# LPCB218_-_HEC1-4.net
KiCad netlist of a schematic drawn in Altium Designer
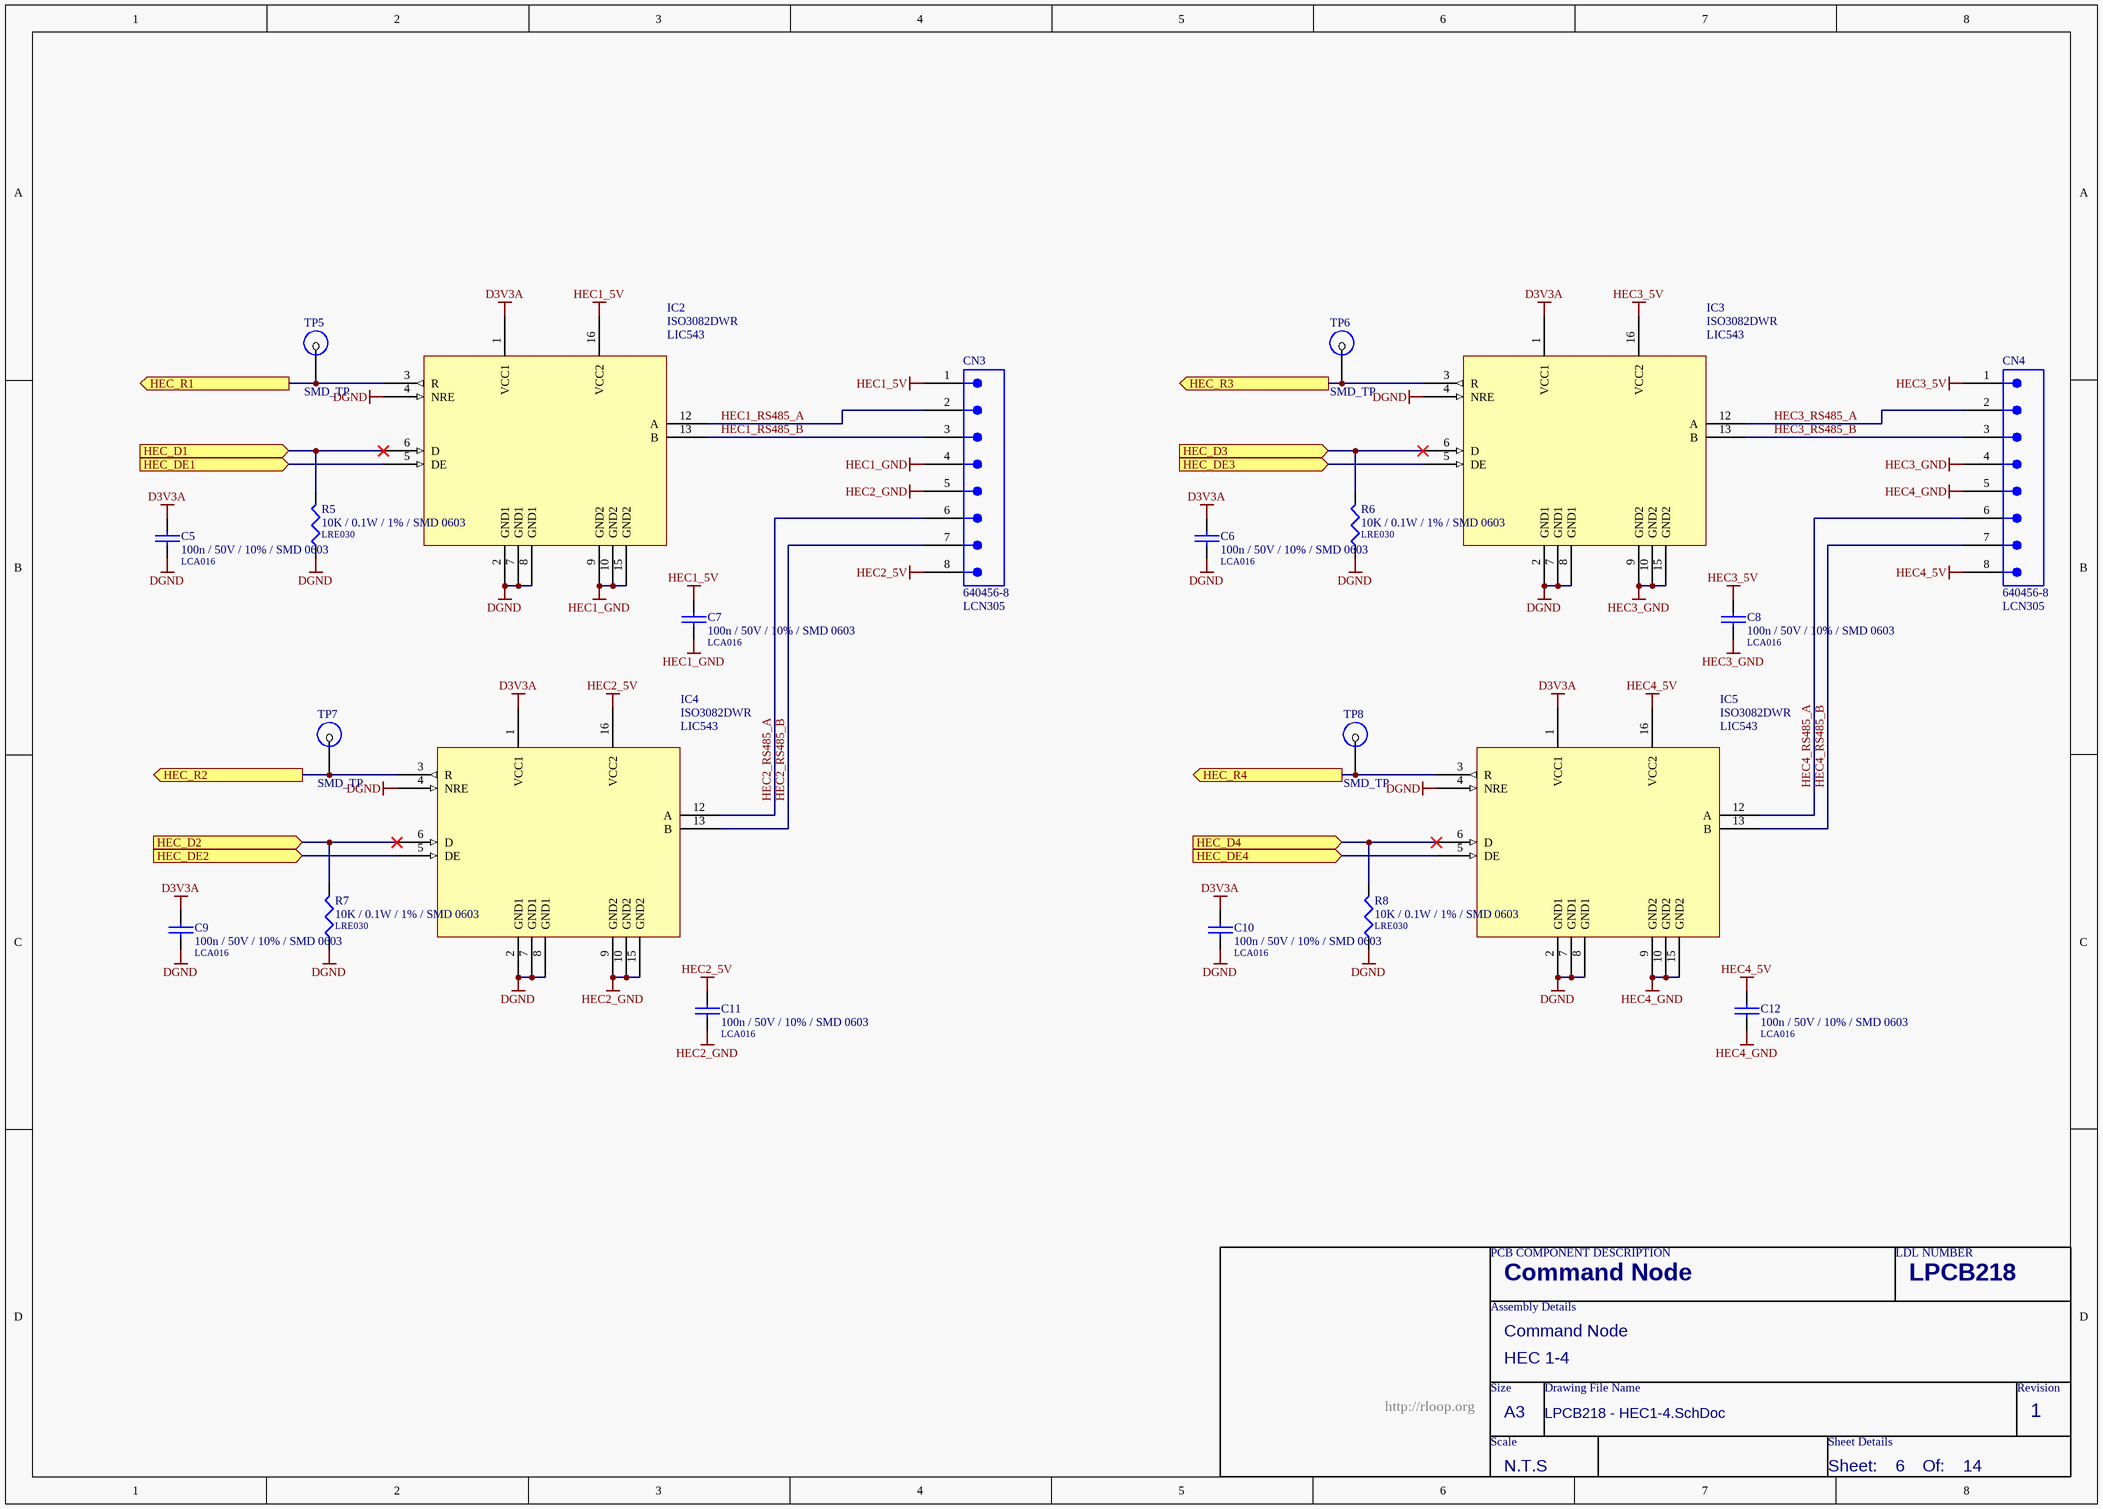
[diagram p0: LPCB218 - HEC1-4.SchDoc]

(export (version "E")
  (design (tool "Eeschema 10.0.6"))
  (components
    (comp (ref "C5")
      (value "100n / 50V / 10% / SMD 0603")
      (footprint "LFP011__CC1608-0603-IPC7351_B")
      (description "Capacitor, Ceramic Chip, 100nF (0.1uF), 50V, 5%, SMD 0603 [LCA016]")
      (fields (field (name "LDL_NUMBER") "LCA016"))
      (libsource (lib "LDL_Capacitors") (part "100n / 50V / 10% / SMD 0603"))
    )
    (comp (ref "C6")
      (value "100n / 50V / 10% / SMD 0603")
      (footprint "LFP011__CC1608-0603-IPC7351_B")
      (description "Capacitor, Ceramic Chip, 100nF (0.1uF), 50V, 5%, SMD 0603 [LCA016]")
      (fields (field (name "LDL_NUMBER") "LCA016"))
      (libsource (lib "LDL_Capacitors") (part "100n / 50V / 10% / SMD 0603"))
    )
    (comp (ref "C7")
      (value "100n / 50V / 10% / SMD 0603")
      (footprint "LFP011__CC1608-0603-IPC7351_B")
      (description "Capacitor, Ceramic Chip, 100nF (0.1uF), 50V, 5%, SMD 0603 [LCA016]")
      (fields (field (name "LDL_NUMBER") "LCA016"))
      (libsource (lib "LDL_Capacitors") (part "100n / 50V / 10% / SMD 0603"))
    )
    (comp (ref "C8")
      (value "100n / 50V / 10% / SMD 0603")
      (footprint "LFP011__CC1608-0603-IPC7351_B")
      (description "Capacitor, Ceramic Chip, 100nF (0.1uF), 50V, 5%, SMD 0603 [LCA016]")
      (fields (field (name "LDL_NUMBER") "LCA016"))
      (libsource (lib "LDL_Capacitors") (part "100n / 50V / 10% / SMD 0603"))
    )
    (comp (ref "C9")
      (value "100n / 50V / 10% / SMD 0603")
      (footprint "LFP011__CC1608-0603-IPC7351_B")
      (description "Capacitor, Ceramic Chip, 100nF (0.1uF), 50V, 5%, SMD 0603 [LCA016]")
      (fields (field (name "LDL_NUMBER") "LCA016"))
      (libsource (lib "LDL_Capacitors") (part "100n / 50V / 10% / SMD 0603"))
    )
    (comp (ref "C10")
      (value "100n / 50V / 10% / SMD 0603")
      (footprint "LFP011__CC1608-0603-IPC7351_B")
      (description "Capacitor, Ceramic Chip, 100nF (0.1uF), 50V, 5%, SMD 0603 [LCA016]")
      (fields (field (name "LDL_NUMBER") "LCA016"))
      (libsource (lib "LDL_Capacitors") (part "100n / 50V / 10% / SMD 0603"))
    )
    (comp (ref "C11")
      (value "100n / 50V / 10% / SMD 0603")
      (footprint "LFP011__CC1608-0603-IPC7351_B")
      (description "Capacitor, Ceramic Chip, 100nF (0.1uF), 50V, 5%, SMD 0603 [LCA016]")
      (fields (field (name "LDL_NUMBER") "LCA016"))
      (libsource (lib "LDL_Capacitors") (part "100n / 50V / 10% / SMD 0603"))
    )
    (comp (ref "C12")
      (value "100n / 50V / 10% / SMD 0603")
      (footprint "LFP011__CC1608-0603-IPC7351_B")
      (description "Capacitor, Ceramic Chip, 100nF (0.1uF), 50V, 5%, SMD 0603 [LCA016]")
      (fields (field (name "LDL_NUMBER") "LCA016"))
      (libsource (lib "LDL_Capacitors") (part "100n / 50V / 10% / SMD 0603"))
    )
    (comp (ref "CN3")
      (value "640456-8")
      (footprint "640456-8")
      (description "Connector, Male Header, 8 Way")
      (fields (field (name "LDL_NUMBER") "LCN305"))
      (libsource (lib "LDL_Connectors") (part "640456-8"))
    )
    (comp (ref "CN4")
      (value "640456-8")
      (footprint "640456-8")
      (description "Connector, Male Header, 8 Way")
      (fields (field (name "LDL_NUMBER") "LCN305"))
      (libsource (lib "LDL_Connectors") (part "640456-8"))
    )
    (comp (ref "IC2")
      (value "ISO3082DWR")
      (footprint "LFP068__SO-G16/G6.9")
      (description "IC, RS485 Isolator, SMD SOIC 16 [LIC543]")
      (fields (field (name "LDL_NUMBER") "LIC543"))
      (libsource (lib "LDL_Semiconductors") (part "ISO3082DWR"))
    )
    (comp (ref "IC3")
      (value "ISO3082DWR")
      (footprint "LFP068__SO-G16/G6.9")
      (description "IC, RS485 Isolator, SMD SOIC 16 [LIC543]")
      (fields (field (name "LDL_NUMBER") "LIC543"))
      (libsource (lib "LDL_Semiconductors") (part "ISO3082DWR"))
    )
    (comp (ref "IC4")
      (value "ISO3082DWR")
      (footprint "LFP068__SO-G16/G6.9")
      (description "IC, RS485 Isolator, SMD SOIC 16 [LIC543]")
      (fields (field (name "LDL_NUMBER") "LIC543"))
      (libsource (lib "LDL_Semiconductors") (part "ISO3082DWR"))
    )
    (comp (ref "IC5")
      (value "ISO3082DWR")
      (footprint "LFP068__SO-G16/G6.9")
      (description "IC, RS485 Isolator, SMD SOIC 16 [LIC543]")
      (fields (field (name "LDL_NUMBER") "LIC543"))
      (libsource (lib "LDL_Semiconductors") (part "ISO3082DWR"))
    )
    (comp (ref "R5")
      (value "10K / 0.1W / 1% / SMD 0603")
      (footprint "LFP020__CR1608-0603-IPC7351_B")
      (description "Resistor, Ceramic Chip, 10K, 0.1W, 1%, SMD 0603 [LRE030]")
      (fields (field (name "LDL_NUMBER") "LRE030"))
      (libsource (lib "LDL_Resistors") (part "10K / 0.1W / 1% / SMD 0603"))
    )
    (comp (ref "R6")
      (value "10K / 0.1W / 1% / SMD 0603")
      (footprint "LFP020__CR1608-0603-IPC7351_B")
      (description "Resistor, Ceramic Chip, 10K, 0.1W, 1%, SMD 0603 [LRE030]")
      (fields (field (name "LDL_NUMBER") "LRE030"))
      (libsource (lib "LDL_Resistors") (part "10K / 0.1W / 1% / SMD 0603"))
    )
    (comp (ref "R7")
      (value "10K / 0.1W / 1% / SMD 0603")
      (footprint "LFP020__CR1608-0603-IPC7351_B")
      (description "Resistor, Ceramic Chip, 10K, 0.1W, 1%, SMD 0603 [LRE030]")
      (fields (field (name "LDL_NUMBER") "LRE030"))
      (libsource (lib "LDL_Resistors") (part "10K / 0.1W / 1% / SMD 0603"))
    )
    (comp (ref "R8")
      (value "10K / 0.1W / 1% / SMD 0603")
      (footprint "LFP020__CR1608-0603-IPC7351_B")
      (description "Resistor, Ceramic Chip, 10K, 0.1W, 1%, SMD 0603 [LRE030]")
      (fields (field (name "LDL_NUMBER") "LRE030"))
      (libsource (lib "LDL_Resistors") (part "10K / 0.1W / 1% / SMD 0603"))
    )
    (comp (ref "TP5")
      (value "SMD_TP")
      (footprint "SMD-TP")
      (description "SMD Test Point")
      (libsource (lib "LDL_Connectors") (part "SMD_TP"))
    )
    (comp (ref "TP6")
      (value "SMD_TP")
      (footprint "SMD-TP")
      (description "SMD Test Point")
      (libsource (lib "LDL_Connectors") (part "SMD_TP"))
    )
    (comp (ref "TP7")
      (value "SMD_TP")
      (footprint "SMD-TP")
      (description "SMD Test Point")
      (libsource (lib "LDL_Connectors") (part "SMD_TP"))
    )
    (comp (ref "TP8")
      (value "SMD_TP")
      (footprint "SMD-TP")
      (description "SMD Test Point")
      (libsource (lib "LDL_Connectors") (part "SMD_TP"))
    )
  )
  (nets
    (net (code "1") (name "/HEC1_RS485_A") (class "Default")
      (node (ref "CN3") (pin "2") (pinfunction "2_2") (pintype "passive"))
      (node (ref "IC2") (pin "12") (pinfunction "A_12") (pintype "passive"))
    )
    (net (code "2") (name "/HEC1_RS485_B") (class "Default")
      (node (ref "CN3") (pin "3") (pinfunction "3_3") (pintype "passive"))
      (node (ref "IC2") (pin "13") (pinfunction "B_13") (pintype "passive"))
    )
    (net (code "3") (name "/HEC2_RS485_A") (class "Default")
      (node (ref "CN3") (pin "6") (pinfunction "6_6") (pintype "passive"))
      (node (ref "IC4") (pin "12") (pinfunction "A_12") (pintype "passive"))
    )
    (net (code "4") (name "/HEC2_RS485_B") (class "Default")
      (node (ref "CN3") (pin "7") (pinfunction "7_7") (pintype "passive"))
      (node (ref "IC4") (pin "13") (pinfunction "B_13") (pintype "passive"))
    )
    (net (code "5") (name "/HEC3_RS485_A") (class "Default")
      (node (ref "CN4") (pin "2") (pinfunction "2_2") (pintype "passive"))
      (node (ref "IC3") (pin "12") (pinfunction "A_12") (pintype "passive"))
    )
    (net (code "6") (name "/HEC3_RS485_B") (class "Default")
      (node (ref "CN4") (pin "3") (pinfunction "3_3") (pintype "passive"))
      (node (ref "IC3") (pin "13") (pinfunction "B_13") (pintype "passive"))
    )
    (net (code "7") (name "/HEC4_RS485_A") (class "Default")
      (node (ref "CN4") (pin "6") (pinfunction "6_6") (pintype "passive"))
      (node (ref "IC5") (pin "12") (pinfunction "A_12") (pintype "passive"))
    )
    (net (code "8") (name "/HEC4_RS485_B") (class "Default")
      (node (ref "CN4") (pin "7") (pinfunction "7_7") (pintype "passive"))
      (node (ref "IC5") (pin "13") (pinfunction "B_13") (pintype "passive"))
    )
    (net (code "9") (name "/HEC_D1") (class "Default")
      (node (ref "IC2") (pin "6") (pinfunction "D_6") (pintype "input"))
      (node (ref "R5") (pin "2") (pintype "passive"))
    )
    (net (code "10") (name "/HEC_D2") (class "Default")
      (node (ref "IC4") (pin "6") (pinfunction "D_6") (pintype "input"))
      (node (ref "R7") (pin "2") (pintype "passive"))
    )
    (net (code "11") (name "/HEC_D3") (class "Default")
      (node (ref "IC3") (pin "6") (pinfunction "D_6") (pintype "input"))
      (node (ref "R6") (pin "2") (pintype "passive"))
    )
    (net (code "12") (name "/HEC_D4") (class "Default")
      (node (ref "IC5") (pin "6") (pinfunction "D_6") (pintype "input"))
      (node (ref "R8") (pin "2") (pintype "passive"))
    )
    (net (code "13") (name "/HEC_DE1") (class "Default")
      (node (ref "IC2") (pin "5") (pinfunction "DE_5") (pintype "input"))
    )
    (net (code "14") (name "/HEC_DE2") (class "Default")
      (node (ref "IC4") (pin "5") (pinfunction "DE_5") (pintype "input"))
    )
    (net (code "15") (name "/HEC_DE3") (class "Default")
      (node (ref "IC3") (pin "5") (pinfunction "DE_5") (pintype "input"))
    )
    (net (code "16") (name "/HEC_DE4") (class "Default")
      (node (ref "IC5") (pin "5") (pinfunction "DE_5") (pintype "input"))
    )
    (net (code "17") (name "/HEC_R1") (class "Default")
      (node (ref "IC2") (pin "3") (pinfunction "R_3") (pintype "output"))
      (node (ref "TP5") (pin "1") (pintype "passive"))
    )
    (net (code "18") (name "/HEC_R2") (class "Default")
      (node (ref "IC4") (pin "3") (pinfunction "R_3") (pintype "output"))
      (node (ref "TP7") (pin "1") (pintype "passive"))
    )
    (net (code "19") (name "/HEC_R3") (class "Default")
      (node (ref "IC3") (pin "3") (pinfunction "R_3") (pintype "output"))
      (node (ref "TP6") (pin "1") (pintype "passive"))
    )
    (net (code "20") (name "/HEC_R4") (class "Default")
      (node (ref "IC5") (pin "3") (pinfunction "R_3") (pintype "output"))
      (node (ref "TP8") (pin "1") (pintype "passive"))
    )
    (net (code "21") (name "D3V3A") (class "Default")
      (node (ref "C10") (pin "1") (pintype "passive"))
      (node (ref "C5") (pin "1") (pintype "passive"))
      (node (ref "C6") (pin "1") (pintype "passive"))
      (node (ref "C9") (pin "1") (pintype "passive"))
      (node (ref "IC2") (pin "1") (pinfunction "VCC1_1") (pintype "power_in"))
      (node (ref "IC3") (pin "1") (pinfunction "VCC1_1") (pintype "power_in"))
      (node (ref "IC4") (pin "1") (pinfunction "VCC1_1") (pintype "power_in"))
      (node (ref "IC5") (pin "1") (pinfunction "VCC1_1") (pintype "power_in"))
    )
    (net (code "22") (name "DGND") (class "Default")
      (node (ref "C10") (pin "2") (pintype "passive"))
      (node (ref "C5") (pin "2") (pintype "passive"))
      (node (ref "C6") (pin "2") (pintype "passive"))
      (node (ref "C9") (pin "2") (pintype "passive"))
      (node (ref "IC2") (pin "2") (pinfunction "GND1_2") (pintype "power_in"))
      (node (ref "IC2") (pin "4") (pinfunction "NRE_4") (pintype "input"))
      (node (ref "IC2") (pin "7") (pinfunction "GND1_7") (pintype "power_in"))
      (node (ref "IC2") (pin "8") (pinfunction "GND1_8") (pintype "power_in"))
      (node (ref "IC3") (pin "2") (pinfunction "GND1_2") (pintype "power_in"))
      (node (ref "IC3") (pin "4") (pinfunction "NRE_4") (pintype "input"))
      (node (ref "IC3") (pin "7") (pinfunction "GND1_7") (pintype "power_in"))
      (node (ref "IC3") (pin "8") (pinfunction "GND1_8") (pintype "power_in"))
      (node (ref "IC4") (pin "2") (pinfunction "GND1_2") (pintype "power_in"))
      (node (ref "IC4") (pin "4") (pinfunction "NRE_4") (pintype "input"))
      (node (ref "IC4") (pin "7") (pinfunction "GND1_7") (pintype "power_in"))
      (node (ref "IC4") (pin "8") (pinfunction "GND1_8") (pintype "power_in"))
      (node (ref "IC5") (pin "2") (pinfunction "GND1_2") (pintype "power_in"))
      (node (ref "IC5") (pin "4") (pinfunction "NRE_4") (pintype "input"))
      (node (ref "IC5") (pin "7") (pinfunction "GND1_7") (pintype "power_in"))
      (node (ref "IC5") (pin "8") (pinfunction "GND1_8") (pintype "power_in"))
      (node (ref "R5") (pin "1") (pintype "passive"))
      (node (ref "R6") (pin "1") (pintype "passive"))
      (node (ref "R7") (pin "1") (pintype "passive"))
      (node (ref "R8") (pin "1") (pintype "passive"))
    )
    (net (code "23") (name "HEC1_5V") (class "Default")
      (node (ref "C7") (pin "1") (pintype "passive"))
      (node (ref "CN3") (pin "1") (pinfunction "1_1") (pintype "passive"))
      (node (ref "IC2") (pin "16") (pinfunction "VCC2_16") (pintype "power_in"))
    )
    (net (code "24") (name "HEC1_GND") (class "Default")
      (node (ref "C7") (pin "2") (pintype "passive"))
      (node (ref "CN3") (pin "4") (pinfunction "4_4") (pintype "passive"))
      (node (ref "IC2") (pin "10") (pinfunction "GND2_10") (pintype "power_in"))
      (node (ref "IC2") (pin "15") (pinfunction "GND2_15") (pintype "power_in"))
      (node (ref "IC2") (pin "9") (pinfunction "GND2_9") (pintype "power_in"))
    )
    (net (code "25") (name "HEC2_5V") (class "Default")
      (node (ref "C11") (pin "1") (pintype "passive"))
      (node (ref "CN3") (pin "8") (pinfunction "8_8") (pintype "passive"))
      (node (ref "IC4") (pin "16") (pinfunction "VCC2_16") (pintype "power_in"))
    )
    (net (code "26") (name "HEC2_GND") (class "Default")
      (node (ref "C11") (pin "2") (pintype "passive"))
      (node (ref "CN3") (pin "5") (pinfunction "5_5") (pintype "passive"))
      (node (ref "IC4") (pin "10") (pinfunction "GND2_10") (pintype "power_in"))
      (node (ref "IC4") (pin "15") (pinfunction "GND2_15") (pintype "power_in"))
      (node (ref "IC4") (pin "9") (pinfunction "GND2_9") (pintype "power_in"))
    )
    (net (code "27") (name "HEC3_5V") (class "Default")
      (node (ref "C8") (pin "1") (pintype "passive"))
      (node (ref "CN4") (pin "1") (pinfunction "1_1") (pintype "passive"))
      (node (ref "IC3") (pin "16") (pinfunction "VCC2_16") (pintype "power_in"))
    )
    (net (code "28") (name "HEC3_GND") (class "Default")
      (node (ref "C8") (pin "2") (pintype "passive"))
      (node (ref "CN4") (pin "4") (pinfunction "4_4") (pintype "passive"))
      (node (ref "IC3") (pin "10") (pinfunction "GND2_10") (pintype "power_in"))
      (node (ref "IC3") (pin "15") (pinfunction "GND2_15") (pintype "power_in"))
      (node (ref "IC3") (pin "9") (pinfunction "GND2_9") (pintype "power_in"))
    )
    (net (code "29") (name "HEC4_5V") (class "Default")
      (node (ref "C12") (pin "1") (pintype "passive"))
      (node (ref "CN4") (pin "8") (pinfunction "8_8") (pintype "passive"))
      (node (ref "IC5") (pin "16") (pinfunction "VCC2_16") (pintype "power_in"))
    )
    (net (code "30") (name "HEC4_GND") (class "Default")
      (node (ref "C12") (pin "2") (pintype "passive"))
      (node (ref "CN4") (pin "5") (pinfunction "5_5") (pintype "passive"))
      (node (ref "IC5") (pin "10") (pinfunction "GND2_10") (pintype "power_in"))
      (node (ref "IC5") (pin "15") (pinfunction "GND2_15") (pintype "power_in"))
      (node (ref "IC5") (pin "9") (pinfunction "GND2_9") (pintype "power_in"))
    )
  )
)
